# stknx_breakout_v14.net
KiCad netlist of a schematic drawn in EAGLE
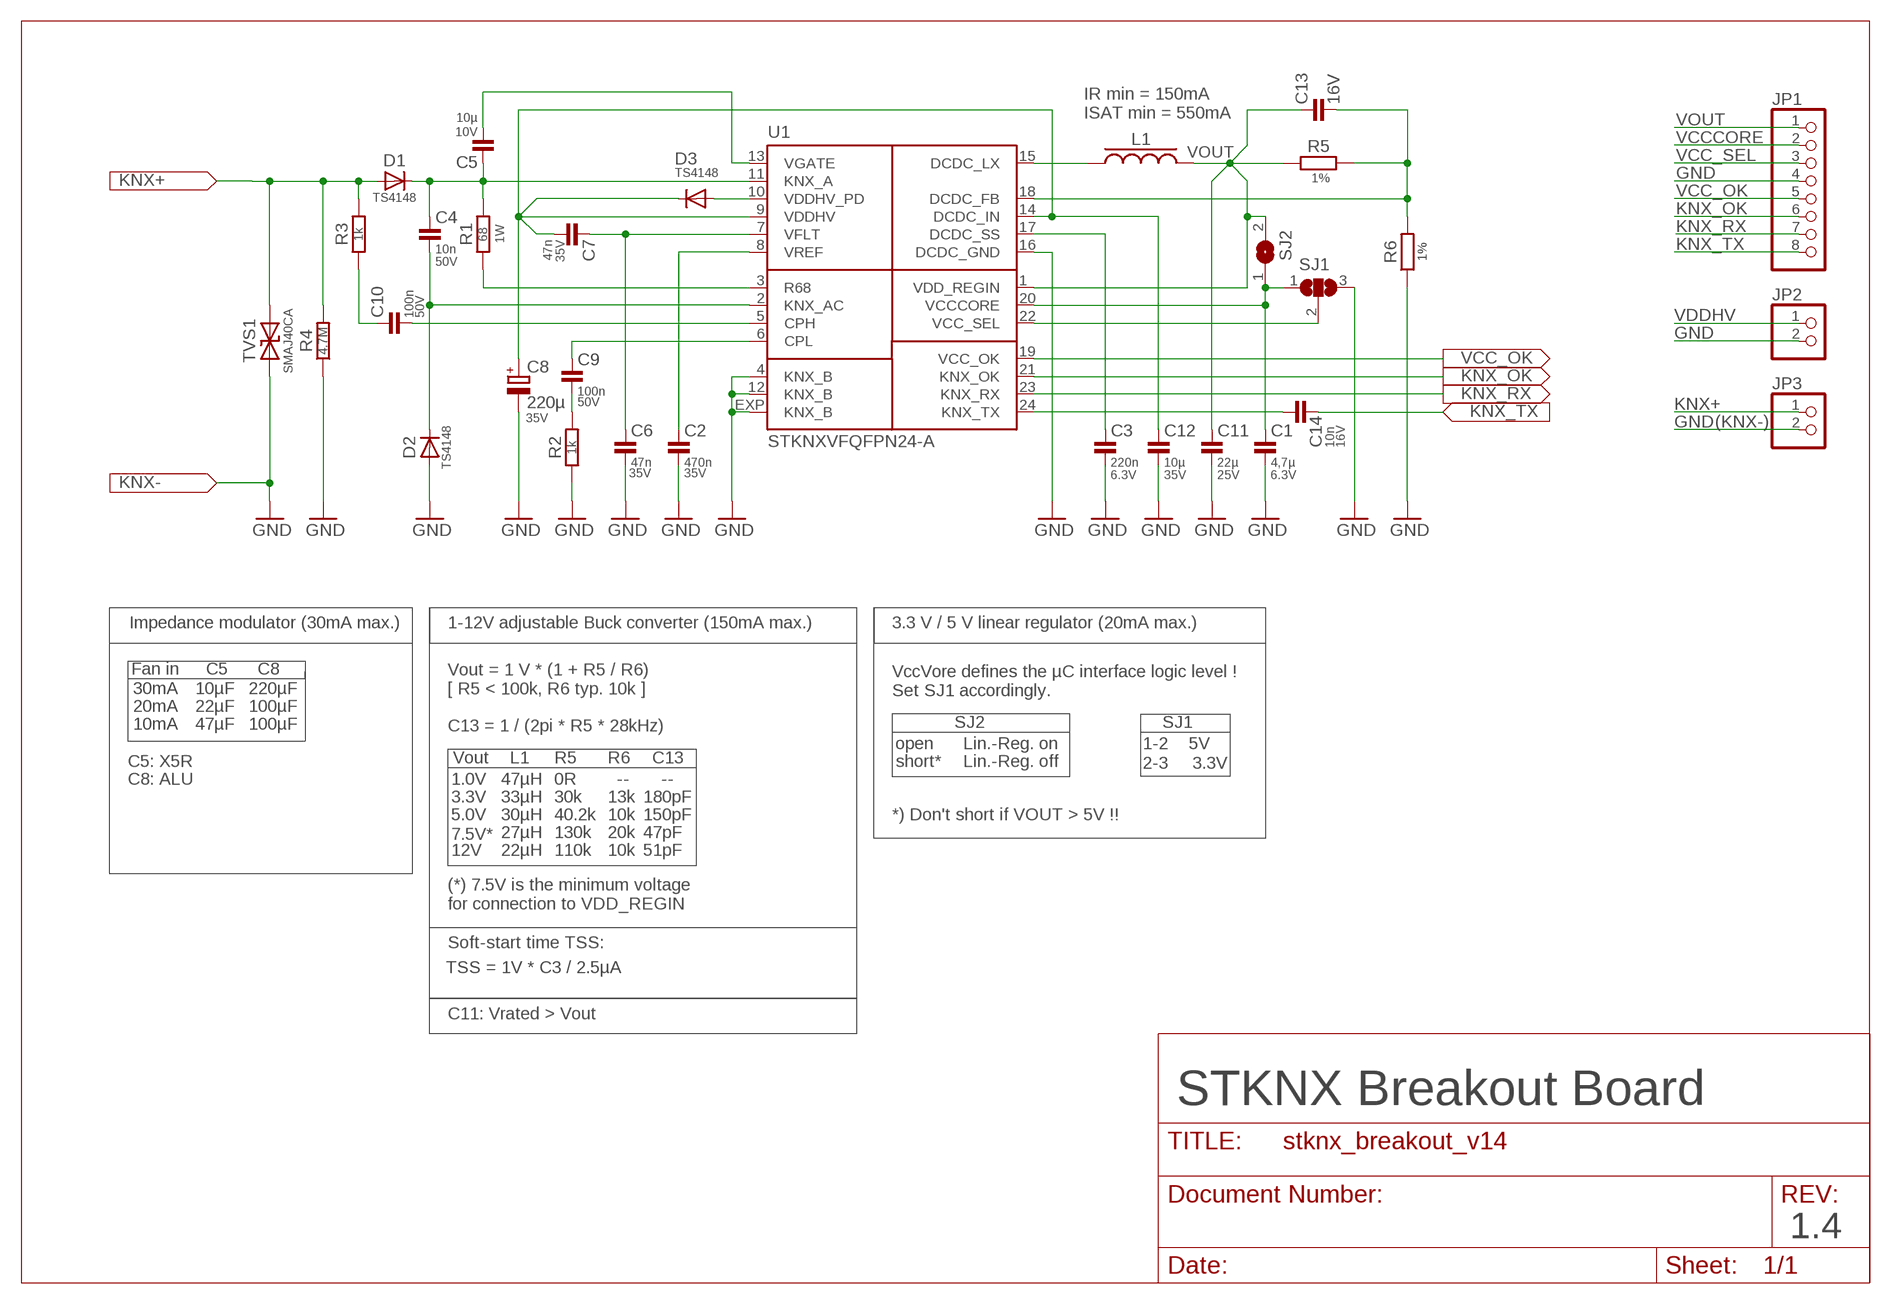
[diagram p0: schematic, sheet 1]

(export (version "E")
  (design (tool "Eeschema 10.0.6"))
  (components
    (comp (ref "C1")
      (value "4,7µ")
      (footprint "eagle-import:C0805")
      (fields (field (name "VOLTAGE") "6.3V"))
      (libsource (lib "eagle-import") (part "C-EUC0805"))
    )
    (comp (ref "C2")
      (value "470n")
      (footprint "eagle-import:C0805")
      (fields (field (name "VOLTAGE") "35V"))
      (libsource (lib "eagle-import") (part "C-EUC0805"))
    )
    (comp (ref "C3")
      (value "220n")
      (footprint "eagle-import:C0805")
      (fields (field (name "VOLTAGE") "6.3V"))
      (libsource (lib "eagle-import") (part "C-EUC0805"))
    )
    (comp (ref "C4")
      (value "10n")
      (footprint "eagle-import:C0805")
      (fields (field (name "VOLTAGE") "50V"))
      (libsource (lib "eagle-import") (part "C-EUC0805"))
    )
    (comp (ref "C5")
      (value "10µ")
      (footprint "eagle-import:C0805")
      (fields (field (name "VOLTAGE") "10V"))
      (libsource (lib "eagle-import") (part "C-EUC0805"))
    )
    (comp (ref "C6")
      (value "47n")
      (footprint "eagle-import:C0805")
      (fields (field (name "VOLTAGE") "35V"))
      (libsource (lib "eagle-import") (part "C-EUC0805"))
    )
    (comp (ref "C7")
      (value "47n")
      (footprint "eagle-import:C0805")
      (fields (field (name "VOLTAGE") "35V"))
      (libsource (lib "eagle-import") (part "C-EUC0805"))
    )
    (comp (ref "C8")
      (value "220µ")
      (footprint "eagle-import:PANASONIC_F")
      (fields (field (name "VOLTAGE") "35V"))
      (libsource (lib "eagle-import") (part "CPOL-EUF"))
    )
    (comp (ref "C9")
      (value "100n")
      (footprint "eagle-import:C0805")
      (fields (field (name "VOLTAGE") "50V"))
      (libsource (lib "eagle-import") (part "C-EUC0805"))
    )
    (comp (ref "C10")
      (value "100n")
      (footprint "eagle-import:C0805")
      (fields (field (name "VOLTAGE") "50V"))
      (libsource (lib "eagle-import") (part "C-EUC0805"))
    )
    (comp (ref "C11")
      (value "22µ")
      (footprint "eagle-import:C0805")
      (fields (field (name "VOLTAGE") "25V"))
      (libsource (lib "eagle-import") (part "C-EUC0805"))
    )
    (comp (ref "C12")
      (value "10µ")
      (footprint "eagle-import:C0805")
      (fields (field (name "VOLTAGE") "35V"))
      (libsource (lib "eagle-import") (part "C-EUC0805"))
    )
    (comp (ref "C13")
      (value "C13")
      (footprint "eagle-import:C0805")
      (fields (field (name "VOLTAGE") "16V"))
      (libsource (lib "eagle-import") (part "C-EUC0805"))
    )
    (comp (ref "C14")
      (value "10n")
      (footprint "eagle-import:C0805")
      (fields (field (name "VOLTAGE") "16V"))
      (libsource (lib "eagle-import") (part "C-EUC0805"))
    )
    (comp (ref "D1")
      (value "TS4148")
      (footprint "eagle-import:0805")
      (libsource (lib "eagle-import") (part "TS4148"))
    )
    (comp (ref "D2")
      (value "TS4148")
      (footprint "eagle-import:0805")
      (libsource (lib "eagle-import") (part "TS4148"))
    )
    (comp (ref "D3")
      (value "TS4148")
      (footprint "eagle-import:0805")
      (libsource (lib "eagle-import") (part "TS4148"))
    )
    (comp (ref "JP1")
      (value "PINHD-1X8")
      (footprint "eagle-import:1X08")
      (libsource (lib "eagle-import") (part "PINHD-1X8"))
    )
    (comp (ref "JP2")
      (value "PINHD-1X2")
      (footprint "eagle-import:1X02")
      (libsource (lib "eagle-import") (part "PINHD-1X2"))
    )
    (comp (ref "JP3")
      (value "PINHD-1X2")
      (footprint "eagle-import:1X02")
      (libsource (lib "eagle-import") (part "PINHD-1X2"))
    )
    (comp (ref "L1")
      (value "L1")
      (footprint "eagle-import:WE-LQS_4025")
      (libsource (lib "eagle-import") (part "WE-LQS_4025_74404043220A"))
    )
    (comp (ref "R1")
      (value "68")
      (footprint "eagle-import:R2512")
      (libsource (lib "eagle-import") (part "R-EU_R2512"))
    )
    (comp (ref "R2")
      (value "1k")
      (footprint "eagle-import:R0805")
      (libsource (lib "eagle-import") (part "R-EU_R0805"))
    )
    (comp (ref "R3")
      (value "1k")
      (footprint "eagle-import:R0805")
      (libsource (lib "eagle-import") (part "R-EU_R0805"))
    )
    (comp (ref "R4")
      (value "4.7M")
      (footprint "eagle-import:R0805")
      (libsource (lib "eagle-import") (part "R-EU_R0805"))
    )
    (comp (ref "R5")
      (value "R5")
      (footprint "eagle-import:R0805")
      (fields (field (name "TOLERANCE") "1%"))
      (libsource (lib "eagle-import") (part "R-EU_R0805"))
    )
    (comp (ref "R6")
      (value "R6")
      (footprint "eagle-import:R0805")
      (fields (field (name "TOLERANCE") "1%"))
      (libsource (lib "eagle-import") (part "R-EU_R0805"))
    )
    (comp (ref "SJ1")
      (value "SJ2W")
      (footprint "eagle-import:SJ_2W")
      (libsource (lib "eagle-import") (part "SJ2W"))
    )
    (comp (ref "SJ2")
      (value "SJW")
      (footprint "eagle-import:SJW")
      (libsource (lib "eagle-import") (part "SJW"))
    )
    (comp (ref "TVS1")
      (value "SMAJ40CA")
      (footprint "eagle-import:DO-214AC(SMA)")
      (libsource (lib "eagle-import") (part "SMAJCA40"))
    )
    (comp (ref "U1")
      (value "STKNXVFQFPN24-A")
      (footprint "eagle-import:VFQFPN24-A")
      (libsource (lib "eagle-import") (part "STKNXVFQFPN24-A"))
    )
  )
  (nets
    (net (code "1") (name "/KNX+") (class "Default")
      (node (ref "D1") (pin "A") (pinfunction "A_A") (pintype "passive"))
      (node (ref "JP3") (pin "1") (pinfunction "1_1") (pintype "passive"))
      (node (ref "R3") (pin "2") (pinfunction "2_2") (pintype "passive"))
      (node (ref "R4") (pin "2") (pinfunction "2_2") (pintype "passive"))
      (node (ref "TVS1") (pin "1") (pinfunction "A1_1") (pintype "passive"))
    )
    (net (code "2") (name "/KNX_OK") (class "Default")
      (node (ref "JP1") (pin "6") (pinfunction "6_6") (pintype "passive"))
      (node (ref "U1") (pin "21") (pinfunction "KNX_OK_21") (pintype "output"))
    )
    (net (code "3") (name "/KNX_RX") (class "Default")
      (node (ref "JP1") (pin "7") (pinfunction "7_7") (pintype "passive"))
      (node (ref "U1") (pin "23") (pinfunction "KNX_RX_23") (pintype "output"))
    )
    (net (code "4") (name "/KNX_TX") (class "Default")
      (node (ref "C14") (pin "2") (pinfunction "2_2") (pintype "passive"))
      (node (ref "JP1") (pin "8") (pinfunction "8_8") (pintype "passive"))
    )
    (net (code "5") (name "/VCCCORE") (class "Default")
      (node (ref "C1") (pin "1") (pinfunction "1_1") (pintype "passive"))
      (node (ref "JP1") (pin "2") (pinfunction "2_2") (pintype "passive"))
      (node (ref "SJ1") (pin "1") (pinfunction "1_1") (pintype "passive"))
      (node (ref "SJ2") (pin "1") (pinfunction "1_1") (pintype "passive"))
      (node (ref "U1") (pin "20") (pinfunction "VCCCORE_20") (pintype "bidirectional"))
    )
    (net (code "6") (name "/VCC_OK") (class "Default")
      (node (ref "JP1") (pin "5") (pinfunction "5_5") (pintype "passive"))
      (node (ref "U1") (pin "19") (pinfunction "VCC_OK_19") (pintype "output"))
    )
    (net (code "7") (name "/VCC_SEL") (class "Default")
      (node (ref "JP1") (pin "3") (pinfunction "3_3") (pintype "passive"))
      (node (ref "SJ1") (pin "2") (pinfunction "2_2") (pintype "passive"))
      (node (ref "U1") (pin "22") (pinfunction "VCC_SEL_22") (pintype "bidirectional"))
    )
    (net (code "8") (name "/VDDHV") (class "Default")
      (node (ref "C12") (pin "1") (pinfunction "1_1") (pintype "passive"))
      (node (ref "C7") (pin "2") (pinfunction "2_2") (pintype "passive"))
      (node (ref "C8") (pin "+") (pinfunction "+_+") (pintype "passive"))
      (node (ref "D3") (pin "C") (pinfunction "C_C") (pintype "passive"))
      (node (ref "JP2") (pin "1") (pinfunction "1_1") (pintype "passive"))
      (node (ref "U1") (pin "14") (pinfunction "DCDC_IN_14") (pintype "bidirectional"))
      (node (ref "U1") (pin "9") (pinfunction "VDDHV_9") (pintype "bidirectional"))
    )
    (net (code "9") (name "/VOUT") (class "Default")
      (node (ref "C11") (pin "1") (pinfunction "1_1") (pintype "passive"))
      (node (ref "C13") (pin "1") (pinfunction "1_1") (pintype "passive"))
      (node (ref "JP1") (pin "1") (pinfunction "1_1") (pintype "passive"))
      (node (ref "L1") (pin "2") (pinfunction "2_2") (pintype "passive"))
      (node (ref "R5") (pin "1") (pinfunction "1_1") (pintype "passive"))
      (node (ref "SJ2") (pin "2") (pinfunction "2_2") (pintype "passive"))
      (node (ref "U1") (pin "1") (pinfunction "VDD_REGIN_1") (pintype "bidirectional"))
    )
    (net (code "10") (name "GND") (class "Default")
      (node (ref "C1") (pin "2") (pinfunction "2_2") (pintype "passive"))
      (node (ref "C11") (pin "2") (pinfunction "2_2") (pintype "passive"))
      (node (ref "C12") (pin "2") (pinfunction "2_2") (pintype "passive"))
      (node (ref "C2") (pin "2") (pinfunction "2_2") (pintype "passive"))
      (node (ref "C3") (pin "2") (pinfunction "2_2") (pintype "passive"))
      (node (ref "C6") (pin "2") (pinfunction "2_2") (pintype "passive"))
      (node (ref "C8") (pin "-") (pinfunction "-_-") (pintype "passive"))
      (node (ref "D2") (pin "A") (pinfunction "A_A") (pintype "passive"))
      (node (ref "JP1") (pin "4") (pinfunction "4_4") (pintype "passive"))
      (node (ref "JP2") (pin "2") (pinfunction "2_2") (pintype "passive"))
      (node (ref "JP3") (pin "2") (pinfunction "2_2") (pintype "passive"))
      (node (ref "R2") (pin "1") (pinfunction "1_1") (pintype "passive"))
      (node (ref "R4") (pin "1") (pinfunction "1_1") (pintype "passive"))
      (node (ref "R6") (pin "1") (pinfunction "1_1") (pintype "passive"))
      (node (ref "SJ1") (pin "3") (pinfunction "3_3") (pintype "passive"))
      (node (ref "TVS1") (pin "2") (pinfunction "A2_2") (pintype "passive"))
      (node (ref "U1") (pin "12") (pinfunction "KNX_B_12") (pintype "power_in"))
      (node (ref "U1") (pin "16") (pinfunction "DCDC_GND_16") (pintype "bidirectional"))
      (node (ref "U1") (pin "4") (pinfunction "KNX_B_4") (pintype "power_in"))
      (node (ref "U1") (pin "EXP") (pinfunction "KNX_B_EXP") (pintype "power_in"))
    )
    (net (code "11") (name "Net-(C9-Pad2)") (class "Default")
      (node (ref "C9") (pin "2") (pinfunction "2_2") (pintype "passive"))
      (node (ref "R2") (pin "2") (pinfunction "2_2") (pintype "passive"))
    )
    (net (code "12") (name "Net-(C10-Pad1)") (class "Default")
      (node (ref "C10") (pin "1") (pinfunction "1_1") (pintype "passive"))
      (node (ref "R3") (pin "1") (pinfunction "1_1") (pintype "passive"))
    )
    (net (code "13") (name "Net-(U1-CPH)") (class "Default")
      (node (ref "C10") (pin "2") (pinfunction "2_2") (pintype "passive"))
      (node (ref "U1") (pin "5") (pinfunction "CPH_5") (pintype "bidirectional"))
    )
    (net (code "14") (name "Net-(U1-CPL)") (class "Default")
      (node (ref "C9") (pin "1") (pinfunction "1_1") (pintype "passive"))
      (node (ref "U1") (pin "6") (pinfunction "CPL_6") (pintype "bidirectional"))
    )
    (net (code "15") (name "Net-(U1-DCDC_FB)") (class "Default")
      (node (ref "C13") (pin "2") (pinfunction "2_2") (pintype "passive"))
      (node (ref "R5") (pin "2") (pinfunction "2_2") (pintype "passive"))
      (node (ref "R6") (pin "2") (pinfunction "2_2") (pintype "passive"))
      (node (ref "U1") (pin "18") (pinfunction "DCDC_FB_18") (pintype "bidirectional"))
    )
    (net (code "16") (name "Net-(U1-DCDC_LX)") (class "Default")
      (node (ref "L1") (pin "1") (pinfunction "1_1") (pintype "passive"))
      (node (ref "U1") (pin "15") (pinfunction "DCDC_LX_15") (pintype "bidirectional"))
    )
    (net (code "17") (name "Net-(U1-DCDC_SS)") (class "Default")
      (node (ref "C3") (pin "1") (pinfunction "1_1") (pintype "passive"))
      (node (ref "U1") (pin "17") (pinfunction "DCDC_SS_17") (pintype "bidirectional"))
    )
    (net (code "18") (name "Net-(U1-KNX_A)") (class "Default")
      (node (ref "C4") (pin "1") (pinfunction "1_1") (pintype "passive"))
      (node (ref "C5") (pin "1") (pinfunction "1_1") (pintype "passive"))
      (node (ref "D1") (pin "C") (pinfunction "C_C") (pintype "passive"))
      (node (ref "R1") (pin "2") (pinfunction "2_2") (pintype "passive"))
      (node (ref "U1") (pin "11") (pinfunction "KNX_A_11") (pintype "bidirectional"))
    )
    (net (code "19") (name "Net-(U1-KNX_AC)") (class "Default")
      (node (ref "C4") (pin "2") (pinfunction "2_2") (pintype "passive"))
      (node (ref "D2") (pin "C") (pinfunction "C_C") (pintype "passive"))
      (node (ref "U1") (pin "2") (pinfunction "KNX_AC_2") (pintype "bidirectional"))
    )
    (net (code "20") (name "Net-(U1-KNX_TX)") (class "Default")
      (node (ref "C14") (pin "1") (pinfunction "1_1") (pintype "passive"))
      (node (ref "U1") (pin "24") (pinfunction "KNX_TX_24") (pintype "input"))
    )
    (net (code "21") (name "Net-(U1-R68)") (class "Default")
      (node (ref "R1") (pin "1") (pinfunction "1_1") (pintype "passive"))
      (node (ref "U1") (pin "3") (pinfunction "R68_3") (pintype "bidirectional"))
    )
    (net (code "22") (name "Net-(U1-VDDHV_PD)") (class "Default")
      (node (ref "D3") (pin "A") (pinfunction "A_A") (pintype "passive"))
      (node (ref "U1") (pin "10") (pinfunction "VDDHV_PD_10") (pintype "bidirectional"))
    )
    (net (code "23") (name "Net-(U1-VFLT)") (class "Default")
      (node (ref "C6") (pin "1") (pinfunction "1_1") (pintype "passive"))
      (node (ref "C7") (pin "1") (pinfunction "1_1") (pintype "passive"))
      (node (ref "U1") (pin "7") (pinfunction "VFLT_7") (pintype "bidirectional"))
    )
    (net (code "24") (name "Net-(U1-VGATE)") (class "Default")
      (node (ref "C5") (pin "2") (pinfunction "2_2") (pintype "passive"))
      (node (ref "U1") (pin "13") (pinfunction "VGATE_13") (pintype "bidirectional"))
    )
    (net (code "25") (name "Net-(U1-VREF)") (class "Default")
      (node (ref "C2") (pin "1") (pinfunction "1_1") (pintype "passive"))
      (node (ref "U1") (pin "8") (pinfunction "VREF_8") (pintype "bidirectional"))
    )
  )
)
